# S6XT10W_POWER.net
KiCad netlist of a schematic drawn in Altium Designer
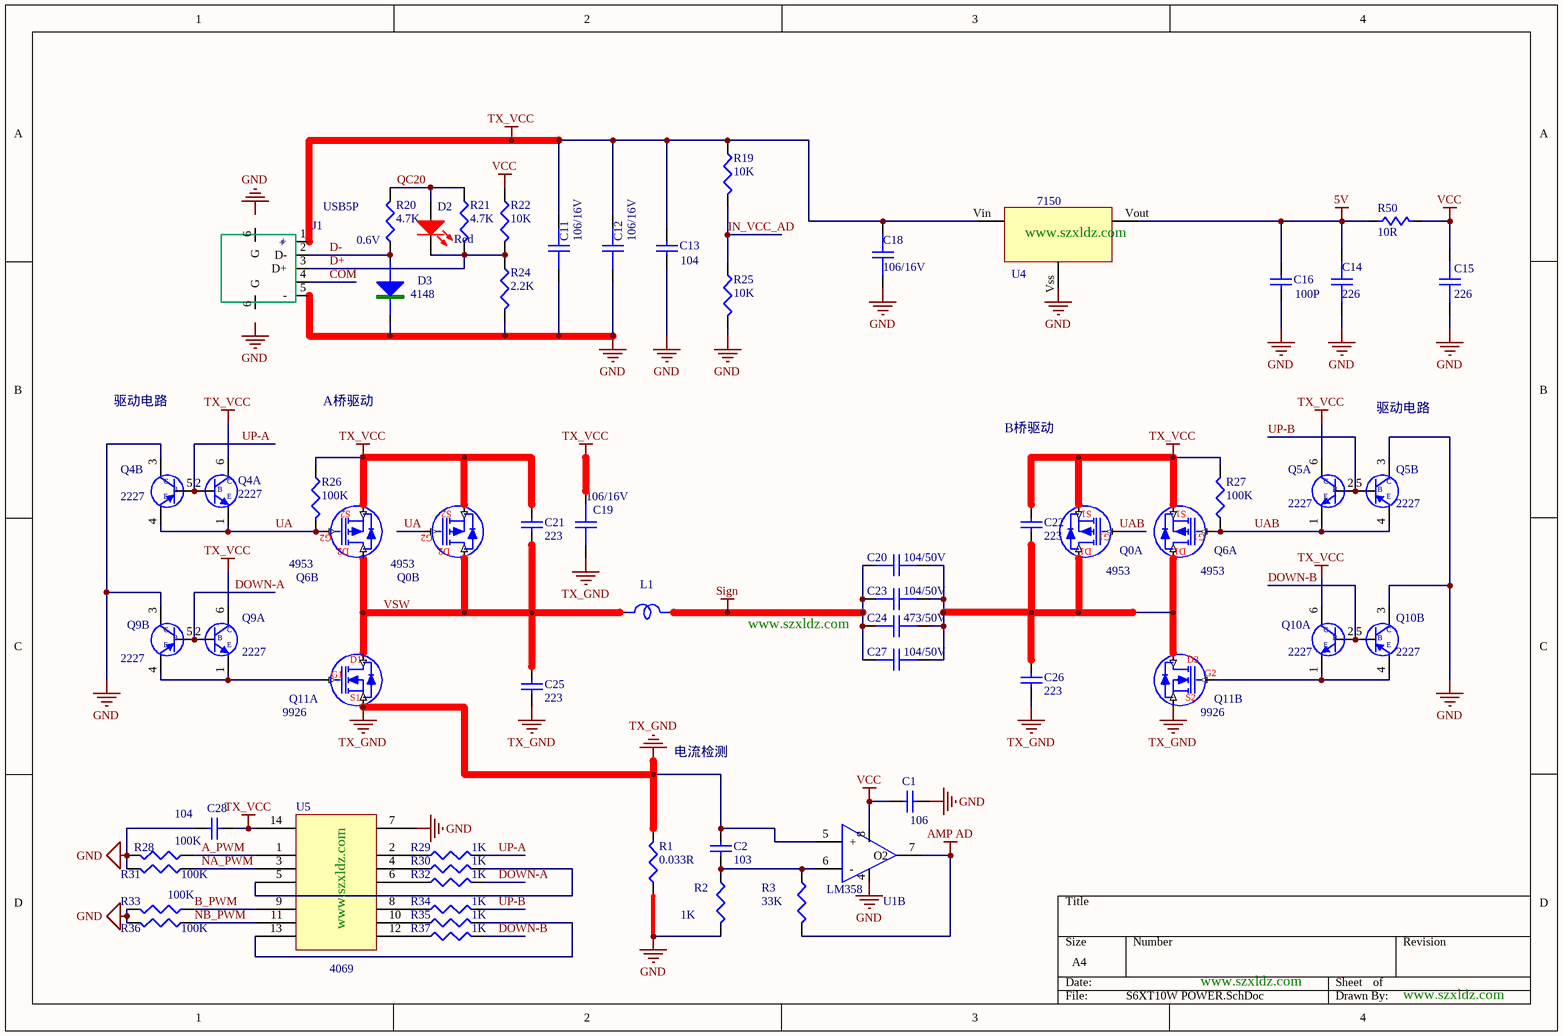
[diagram p0: S6XT10W POWER.SchDoc]

(export (version "E")
  (design (tool "Eeschema 10.0.6"))
  (components
    (comp (ref "C1")
      (value "106")
      (footprint "C0603")
      (description "Capacitor")
      (fields (field (name "PUBLISHER") "Altium Limited"))
      (libsource (lib "*") (part "Cap"))
    )
    (comp (ref "C2")
      (value "103")
      (footprint "C0402")
      (description "Capacitor")
      (fields (field (name "PUBLISHER") "Altium Limited"))
      (libsource (lib "*") (part "Cap"))
    )
    (comp (ref "C11") (value "106/16V") (footprint "C0805") (libsource (lib "*") (part "CH")))
    (comp (ref "C12") (value "106/16V") (footprint "C0805") (libsource (lib "*") (part "CH")))
    (comp (ref "C13")
      (value "104")
      (footprint "C0402")
      (description "Capacitor")
      (fields (field (name "PUBLISHER") "Altium Limited"))
      (libsource (lib "*") (part "Cap"))
    )
    (comp (ref "C14") (value "226") (footprint "C0805") (libsource (lib "*") (part "CH")))
    (comp (ref "C15") (value "226") (footprint "C0805") (libsource (lib "*") (part "CH")))
    (comp (ref "C16")
      (value "100P")
      (footprint "C0402")
      (description "Capacitor")
      (fields (field (name "PUBLISHER") "Altium Limited"))
      (libsource (lib "*") (part "Cap"))
    )
    (comp (ref "C18") (value "106/16V") (footprint "C0805") (libsource (lib "*") (part "CH")))
    (comp (ref "C19") (value "106/16V") (footprint "C0805") (libsource (lib "*") (part "CH")))
    (comp (ref "C20") (value "104/50V") (footprint "C1206") (libsource (lib "*") (part "CH")))
    (comp (ref "C21")
      (value "223")
      (footprint "C0603")
      (description "Capacitor")
      (fields (field (name "PUBLISHER") "Altium Limited"))
      (libsource (lib "*") (part "Cap"))
    )
    (comp (ref "C22")
      (value "223")
      (footprint "C0603")
      (description "Capacitor")
      (fields (field (name "PUBLISHER") "Altium Limited"))
      (libsource (lib "*") (part "Cap"))
    )
    (comp (ref "C23") (value "104/50V") (footprint "C1206") (libsource (lib "*") (part "CH")))
    (comp (ref "C24") (value "473/50V") (footprint "C1206") (libsource (lib "*") (part "CH")))
    (comp (ref "C25")
      (value "223")
      (footprint "C1206")
      (description "Capacitor")
      (fields (field (name "PUBLISHER") "Altium Limited"))
      (libsource (lib "*") (part "Cap"))
    )
    (comp (ref "C26")
      (value "223")
      (footprint "C0603")
      (description "Capacitor")
      (fields (field (name "PUBLISHER") "Altium Limited"))
      (libsource (lib "*") (part "Cap"))
    )
    (comp (ref "C27") (value "104/50V") (footprint "C1206") (libsource (lib "*") (part "CH")))
    (comp (ref "C28")
      (value "104")
      (footprint "C0402")
      (description "Capacitor")
      (fields (field (name "PUBLISHER") "Altium Limited"))
      (libsource (lib "*") (part "Cap"))
    )
    (comp (ref "D2") (value "Red") (footprint "LED0603") (libsource (lib "XiaoQiang") (part "LED02")))
    (comp (ref "D3")
      (value "4148")
      (footprint "SOD323")
      (description "1N4001")
      (libsource (lib "*") (part "D0"))
    )
    (comp (ref "J1") (value "USB5P") (footprint "USB -MRO05") (libsource (lib "lxzschlib") (part "USB5P")))
    (comp (ref "L1") (value "~") (footprint "l5mm") (description "1uH") (libsource (lib "*") (part "L")))
    (comp (ref "Q0") (value "4953") (footprint "SOP8D") (libsource (lib "lxzschlib") (part "MOSFETP2")))
    (comp (ref "Q4") (value "2227") (footprint "SOT363") (libsource (lib "lxzschlib") (part "N+PS")))
    (comp (ref "Q5") (value "2227") (footprint "SOT363") (libsource (lib "") (part "N+PS_1")))
    (comp (ref "Q6") (value "4953") (footprint "SOP8D") (libsource (lib "lxzschlib") (part "MOSFETP2")))
    (comp (ref "Q9") (value "2227") (footprint "SOT363") (libsource (lib "") (part "N+PS_1")))
    (comp (ref "Q10") (value "2227") (footprint "SOT363") (libsource (lib "lxzschlib") (part "N+PS")))
    (comp (ref "Q11") (value "9926") (footprint "SOP8D") (libsource (lib "lxzschlib") (part "MOSFETN2")))
    (comp (ref "R1") (value "0.033R") (footprint "R0805") (description "1K") (libsource (lib "*") (part "R")))
    (comp (ref "R2") (value "1K") (footprint "R0402") (libsource (lib "*") (part "R")))
    (comp (ref "R3") (value "33K") (footprint "R0402") (description "1K") (libsource (lib "*") (part "R")))
    (comp (ref "R19") (value "10K") (footprint "R0402") (description "1K") (libsource (lib "*") (part "R")))
    (comp (ref "R20") (value "4.7K") (footprint "R0402") (description "1K") (libsource (lib "*") (part "R")))
    (comp (ref "R21") (value "4.7K") (footprint "R0402") (description "1K") (libsource (lib "*") (part "R")))
    (comp (ref "R22") (value "10K") (footprint "R0402") (description "1K") (libsource (lib "*") (part "R")))
    (comp (ref "R24") (value "2.2K") (footprint "R0402") (description "1K") (libsource (lib "*") (part "R")))
    (comp (ref "R25") (value "10K") (footprint "R0402") (description "1K") (libsource (lib "*") (part "R")))
    (comp (ref "R26") (value "100K") (footprint "R0402") (description "1K") (libsource (lib "*") (part "R")))
    (comp (ref "R27") (value "100K") (footprint "R0402") (description "1K") (libsource (lib "*") (part "R")))
    (comp (ref "R28") (value "100K") (footprint "R0402") (description "1K") (libsource (lib "*") (part "R")))
    (comp (ref "R29") (value "1K") (footprint "R0402") (libsource (lib "*") (part "R")))
    (comp (ref "R30") (value "1K") (footprint "R0402") (libsource (lib "*") (part "R")))
    (comp (ref "R31") (value "100K") (footprint "R0402") (description "1K") (libsource (lib "*") (part "R")))
    (comp (ref "R32") (value "1K") (footprint "R0402") (libsource (lib "*") (part "R")))
    (comp (ref "R33") (value "100K") (footprint "R0402") (description "1K") (libsource (lib "*") (part "R")))
    (comp (ref "R34") (value "1K") (footprint "R0402") (libsource (lib "*") (part "R")))
    (comp (ref "R35") (value "1K") (footprint "R0402") (libsource (lib "*") (part "R")))
    (comp (ref "R36") (value "100K") (footprint "R0402") (description "1K") (libsource (lib "*") (part "R")))
    (comp (ref "R37") (value "1K") (footprint "R0402") (libsource (lib "*") (part "R")))
    (comp (ref "R50") (value "10R") (footprint "R0402") (libsource (lib "Xin Lang") (part "Res01")))
    (comp (ref "U1") (value "LM358") (footprint "SOP8") (libsource (lib "lxzschlib") (part "4558")))
    (comp (ref "U4") (value "7150") (footprint "SOT89a") (libsource (lib "*") (part "VOLTREG")))
    (comp (ref "U5") (value "4069") (footprint "SOP14") (libsource (lib "Schlib1") (part "CD4069")))
  )
  (nets
    (net (code "1") (name "/A_PWM") (class "Default")
      (node (ref "R28") (pin "1") (pintype "passive"))
      (node (ref "U5") (pin "1") (pintype "passive"))
    )
    (net (code "2") (name "/B_PWM") (class "Default")
      (node (ref "R33") (pin "1") (pintype "passive"))
      (node (ref "U5") (pin "9") (pintype "passive"))
    )
    (net (code "3") (name "/COM") (class "Default") (node (ref "J1") (pin "4") (pintype "passive")))
    (net (code "4") (name "/D+") (class "Default")
      (node (ref "D2") (pin "2") (pinfunction "K_2") (pintype "passive"))
      (node (ref "J1") (pin "3") (pinfunction "D+_3") (pintype "passive"))
      (node (ref "R21") (pin "1") (pintype "passive"))
      (node (ref "R22") (pin "1") (pintype "passive"))
      (node (ref "R24") (pin "2") (pintype "passive"))
    )
    (net (code "5") (name "/D-") (class "Default")
      (node (ref "D3") (pin "1") (pintype "passive"))
      (node (ref "J1") (pin "2") (pinfunction "D-_2") (pintype "passive"))
      (node (ref "R20") (pin "2") (pintype "passive"))
    )
    (net (code "6") (name "/DOWN-A") (class "Default")
      (node (ref "Q9") (pin "2") (pinfunction "B_2") (pintype "passive"))
      (node (ref "Q9") (pin "5") (pinfunction "B_5") (pintype "passive"))
      (node (ref "R32") (pin "2") (pintype "passive"))
    )
    (net (code "7") (name "/DOWN-B") (class "Default")
      (node (ref "Q10") (pin "2") (pinfunction "B_2") (pintype "passive"))
      (node (ref "Q10") (pin "5") (pinfunction "B_5") (pintype "passive"))
      (node (ref "R37") (pin "2") (pintype "passive"))
    )
    (net (code "8") (name "/IN_VCC_AD") (class "Default")
      (node (ref "R19") (pin "1") (pintype "passive"))
      (node (ref "R25") (pin "2") (pintype "passive"))
    )
    (net (code "9") (name "/NA_PWM") (class "Default")
      (node (ref "R31") (pin "1") (pintype "passive"))
      (node (ref "U5") (pin "3") (pintype "passive"))
    )
    (net (code "10") (name "/NB_PWM") (class "Default")
      (node (ref "R36") (pin "1") (pintype "passive"))
      (node (ref "U5") (pin "11") (pintype "passive"))
    )
    (net (code "11") (name "/QC20") (class "Default")
      (node (ref "D2") (pin "1") (pinfunction "A_1") (pintype "passive"))
      (node (ref "R20") (pin "1") (pintype "passive"))
      (node (ref "R21") (pin "2") (pintype "passive"))
    )
    (net (code "12") (name "/UA") (class "Default")
      (node (ref "Q0") (pin "B2") (pinfunction "G2_B2") (pintype "input"))
      (node (ref "Q4") (pin "1") (pinfunction "E_1") (pintype "passive"))
      (node (ref "Q4") (pin "4") (pinfunction "E_4") (pintype "passive"))
      (node (ref "Q6") (pin "B2") (pinfunction "G2_B2") (pintype "input"))
      (node (ref "R26") (pin "2") (pintype "passive"))
    )
    (net (code "13") (name "/UAB") (class "Default")
      (node (ref "Q0") (pin "B1") (pinfunction "G1_B1") (pintype "input"))
      (node (ref "Q5") (pin "1") (pinfunction "E_1") (pintype "passive"))
      (node (ref "Q5") (pin "4") (pinfunction "E_4") (pintype "passive"))
      (node (ref "Q6") (pin "B1") (pinfunction "G1_B1") (pintype "input"))
      (node (ref "R27") (pin "1") (pintype "passive"))
    )
    (net (code "14") (name "/UP-A") (class "Default")
      (node (ref "Q4") (pin "2") (pinfunction "B_2") (pintype "passive"))
      (node (ref "Q4") (pin "5") (pinfunction "B_5") (pintype "passive"))
      (node (ref "R29") (pin "2") (pintype "passive"))
    )
    (net (code "15") (name "/UP-B") (class "Default")
      (node (ref "Q5") (pin "2") (pinfunction "B_2") (pintype "passive"))
      (node (ref "Q5") (pin "5") (pinfunction "B_5") (pintype "passive"))
      (node (ref "R34") (pin "2") (pintype "passive"))
    )
    (net (code "16") (name "/VSW") (class "Default")
      (node (ref "C21") (pin "1") (pinfunction "1_1") (pintype "passive"))
      (node (ref "C25") (pin "2") (pinfunction "2_2") (pintype "passive"))
      (node (ref "L1") (pin "1") (pintype "passive"))
      (node (ref "Q0") (pin "C2") (pinfunction "D2_C2") (pintype "input"))
      (node (ref "Q11") (pin "C1") (pinfunction "D1_C1") (pintype "input"))
      (node (ref "Q6") (pin "C2") (pinfunction "D2_C2") (pintype "input"))
    )
    (net (code "17") (name "5V") (class "Default")
      (node (ref "C14") (pin "1") (pintype "passive"))
      (node (ref "C16") (pin "1") (pinfunction "1_1") (pintype "passive"))
      (node (ref "R50") (pin "1") (pinfunction "1_1") (pintype "passive"))
      (node (ref "U4") (pin "Vout") (pintype "passive"))
    )
    (net (code "18") (name "AMP AD") (class "Default")
      (node (ref "R3") (pin "2") (pintype "passive"))
      (node (ref "U1") (pin "7") (pinfunction "O2_7") (pintype "passive"))
    )
    (net (code "19") (name "GND") (class "Default")
      (node (ref "C1") (pin "1") (pinfunction "1_1") (pintype "passive"))
      (node (ref "C11") (pin "2") (pintype "passive"))
      (node (ref "C12") (pin "2") (pintype "passive"))
      (node (ref "C13") (pin "2") (pinfunction "2_2") (pintype "passive"))
      (node (ref "C14") (pin "2") (pintype "passive"))
      (node (ref "C15") (pin "1") (pintype "passive"))
      (node (ref "C16") (pin "2") (pinfunction "2_2") (pintype "passive"))
      (node (ref "C18") (pin "2") (pintype "passive"))
      (node (ref "C28") (pin "1") (pinfunction "1_1") (pintype "passive"))
      (node (ref "D3") (pin "2") (pintype "passive"))
      (node (ref "J1") (pin "5") (pinfunction "-_5") (pintype "passive"))
      (node (ref "Q10") (pin "3") (pinfunction "C_3") (pintype "passive"))
      (node (ref "Q4") (pin "3") (pinfunction "C_3") (pintype "passive"))
      (node (ref "Q5") (pin "3") (pinfunction "C_3") (pintype "passive"))
      (node (ref "Q9") (pin "3") (pinfunction "C_3") (pintype "passive"))
      (node (ref "R1") (pin "1") (pintype "passive"))
      (node (ref "R2") (pin "2") (pintype "passive"))
      (node (ref "R24") (pin "1") (pintype "passive"))
      (node (ref "R25") (pin "1") (pintype "passive"))
      (node (ref "R28") (pin "2") (pintype "passive"))
      (node (ref "R31") (pin "2") (pintype "passive"))
      (node (ref "R33") (pin "2") (pintype "passive"))
      (node (ref "R36") (pin "2") (pintype "passive"))
      (node (ref "U1") (pin "4") (pintype "passive"))
      (node (ref "U4") (pin "Vss") (pintype "passive"))
      (node (ref "U5") (pin "7") (pintype "passive"))
    )
    (net (code "20") (name "Net-(Q0A-D1)") (class "Default")
      (node (ref "C20") (pin "2") (pintype "passive"))
      (node (ref "C22") (pin "1") (pinfunction "1_1") (pintype "passive"))
      (node (ref "C23") (pin "2") (pintype "passive"))
      (node (ref "C24") (pin "2") (pintype "passive"))
      (node (ref "C26") (pin "2") (pinfunction "2_2") (pintype "passive"))
      (node (ref "C27") (pin "2") (pintype "passive"))
      (node (ref "Q0") (pin "C1") (pinfunction "D1_C1") (pintype "input"))
      (node (ref "Q11") (pin "C2") (pinfunction "D2_C2") (pintype "input"))
      (node (ref "Q6") (pin "C1") (pinfunction "D1_C1") (pintype "input"))
    )
    (net (code "21") (name "Net-(Q10A-E)") (class "Default")
      (node (ref "Q10") (pin "1") (pinfunction "E_1") (pintype "passive"))
      (node (ref "Q10") (pin "4") (pinfunction "E_4") (pintype "passive"))
      (node (ref "Q11") (pin "B2") (pinfunction "G2_B2") (pintype "input"))
    )
    (net (code "22") (name "Net-(Q11A-G1)") (class "Default")
      (node (ref "Q11") (pin "B1") (pinfunction "G1_B1") (pintype "input"))
      (node (ref "Q9") (pin "1") (pinfunction "E_1") (pintype "passive"))
      (node (ref "Q9") (pin "4") (pinfunction "E_4") (pintype "passive"))
    )
    (net (code "23") (name "Net-(R29-Pad1)") (class "Default")
      (node (ref "R29") (pin "1") (pintype "passive"))
      (node (ref "U5") (pin "2") (pintype "passive"))
    )
    (net (code "24") (name "Net-(R30-Pad1)") (class "Default")
      (node (ref "R30") (pin "1") (pintype "passive"))
      (node (ref "U5") (pin "4") (pintype "passive"))
    )
    (net (code "25") (name "Net-(R30-Pad2)") (class "Default")
      (node (ref "R30") (pin "2") (pintype "passive"))
      (node (ref "U5") (pin "5") (pintype "passive"))
    )
    (net (code "26") (name "Net-(R32-Pad1)") (class "Default")
      (node (ref "R32") (pin "1") (pintype "passive"))
      (node (ref "U5") (pin "6") (pintype "passive"))
    )
    (net (code "27") (name "Net-(R34-Pad1)") (class "Default")
      (node (ref "R34") (pin "1") (pintype "passive"))
      (node (ref "U5") (pin "8") (pintype "passive"))
    )
    (net (code "28") (name "Net-(R35-Pad1)") (class "Default")
      (node (ref "R35") (pin "1") (pintype "passive"))
      (node (ref "U5") (pin "10") (pintype "passive"))
    )
    (net (code "29") (name "Net-(R35-Pad2)") (class "Default")
      (node (ref "R35") (pin "2") (pintype "passive"))
      (node (ref "U5") (pin "13") (pintype "passive"))
    )
    (net (code "30") (name "Net-(R37-Pad1)") (class "Default")
      (node (ref "R37") (pin "1") (pintype "passive"))
      (node (ref "U5") (pin "12") (pintype "passive"))
    )
    (net (code "31") (name "Net-(U1B--)") (class "Default")
      (node (ref "C2") (pin "2") (pinfunction "2_2") (pintype "passive"))
      (node (ref "R2") (pin "1") (pintype "passive"))
      (node (ref "R3") (pin "1") (pintype "passive"))
      (node (ref "U1") (pin "6") (pinfunction "-_6") (pintype "passive"))
    )
    (net (code "32") (name "Sign") (class "Default")
      (node (ref "C20") (pin "1") (pintype "passive"))
      (node (ref "C23") (pin "1") (pintype "passive"))
      (node (ref "C24") (pin "1") (pintype "passive"))
      (node (ref "C27") (pin "1") (pintype "passive"))
      (node (ref "L1") (pin "2") (pintype "passive"))
    )
    (net (code "33") (name "TX_GND") (class "Default")
      (node (ref "C19") (pin "2") (pintype "passive"))
      (node (ref "C2") (pin "1") (pinfunction "1_1") (pintype "passive"))
      (node (ref "C25") (pin "1") (pinfunction "1_1") (pintype "passive"))
      (node (ref "C26") (pin "1") (pinfunction "1_1") (pintype "passive"))
      (node (ref "Q11") (pin "E1") (pinfunction "S1_E1") (pintype "input"))
      (node (ref "Q11") (pin "E2") (pinfunction "S2_E2") (pintype "input"))
      (node (ref "R1") (pin "2") (pintype "passive"))
      (node (ref "U1") (pin "5") (pinfunction "+_5") (pintype "passive"))
    )
    (net (code "34") (name "TX_VCC") (class "Default")
      (node (ref "C11") (pin "1") (pintype "passive"))
      (node (ref "C12") (pin "1") (pintype "passive"))
      (node (ref "C13") (pin "1") (pinfunction "1_1") (pintype "passive"))
      (node (ref "C18") (pin "1") (pintype "passive"))
      (node (ref "C19") (pin "1") (pintype "passive"))
      (node (ref "C21") (pin "2") (pinfunction "2_2") (pintype "passive"))
      (node (ref "C22") (pin "2") (pinfunction "2_2") (pintype "passive"))
      (node (ref "C28") (pin "2") (pinfunction "2_2") (pintype "passive"))
      (node (ref "J1") (pin "1") (pinfunction "+_1") (pintype "passive"))
      (node (ref "Q0") (pin "E1") (pinfunction "S1_E1") (pintype "input"))
      (node (ref "Q0") (pin "E2") (pinfunction "S2_E2") (pintype "input"))
      (node (ref "Q10") (pin "6") (pinfunction "C_6") (pintype "passive"))
      (node (ref "Q4") (pin "6") (pinfunction "C_6") (pintype "passive"))
      (node (ref "Q5") (pin "6") (pinfunction "C_6") (pintype "passive"))
      (node (ref "Q6") (pin "E1") (pinfunction "S1_E1") (pintype "input"))
      (node (ref "Q6") (pin "E2") (pinfunction "S2_E2") (pintype "input"))
      (node (ref "Q9") (pin "6") (pinfunction "C_6") (pintype "passive"))
      (node (ref "R19") (pin "2") (pintype "passive"))
      (node (ref "R26") (pin "1") (pintype "passive"))
      (node (ref "R27") (pin "2") (pintype "passive"))
      (node (ref "U4") (pin "Vin") (pintype "passive"))
      (node (ref "U5") (pin "14") (pintype "passive"))
    )
    (net (code "35") (name "VCC") (class "Default")
      (node (ref "C1") (pin "2") (pinfunction "2_2") (pintype "passive"))
      (node (ref "C15") (pin "2") (pintype "passive"))
      (node (ref "R22") (pin "2") (pintype "passive"))
      (node (ref "R50") (pin "2") (pinfunction "2_2") (pintype "passive"))
      (node (ref "U1") (pin "8") (pintype "passive"))
    )
    (net (code "36") (name "unconnected-(J1-G-Pad6)") (class "Default")
      (node (ref "J1") (pin "6") (pinfunction "G_6") (pintype "passive"))
    )
    (net (code "37") (name "unconnected-(J1-G-Pad6)_1") (class "Default")
      (node (ref "J1") (pin "6") (pinfunction "G_6") (pintype "passive"))
    )
  )
)
